# Camera.net
KiCad netlist of a schematic drawn in Altium Designer
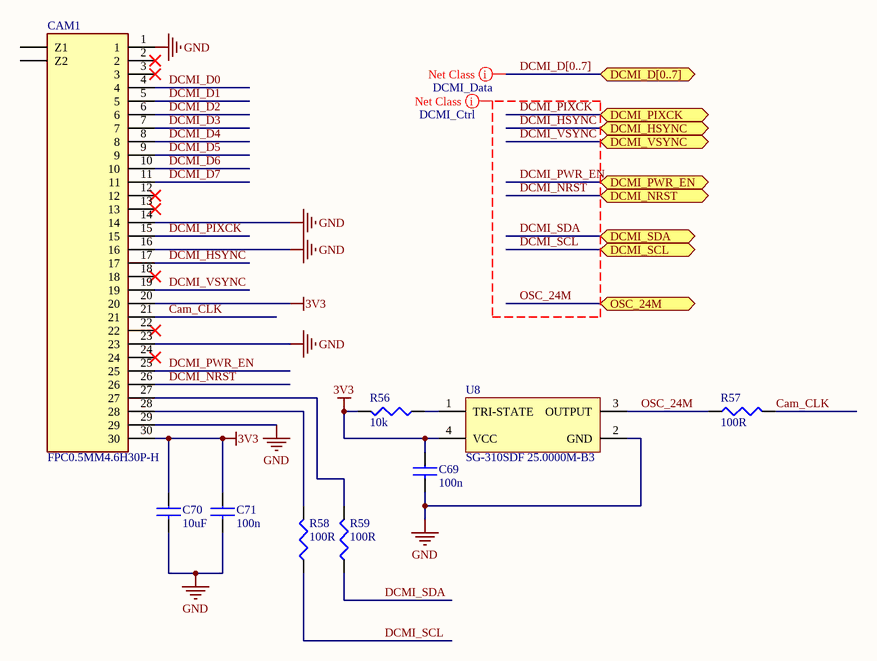
[diagram p0: Camera.SchDoc]

(export (version "E")
  (design (tool "Eeschema 10.0.6"))
  (components
    (comp (ref "C69")
      (value "100n")
      (footprint "C0402")
      (description "CAP CER .10UF 50V X5R 10% 0402")
      (fields
        (field (name "MANUFACTURER") "TDK Corporation")
        (field (name "MANUFACTURER PART NUMBER") "C1005X5R1H104K")
      )
      (libsource (lib "iMX6_Rex_Development_Baseboard_V1I1") (part "C1005X5R1H104K"))
    )
    (comp (ref "C70")
      (value "10uF")
      (footprint "C0402")
      (description "CAP CER 4.7UF 10V 20% X5R 0402")
      (fields
        (field (name "MANUFACTURER") "TDK Corporation")
        (field (name "MANUFACTURER PART NUMBER") "C1005X5R1A475M")
        (field (name ".CHECKED PCB") "RF")
        (field (name ".CHECKED SCH") "RF")
      )
      (libsource (lib "iMX6_Rex_Development_Baseboard_V1I1") (part "C1005X5R1A475M"))
    )
    (comp (ref "C71")
      (value "100n")
      (footprint "C0402")
      (description "CAP CER .10UF 50V X5R 10% 0402")
      (fields
        (field (name "MANUFACTURER") "TDK Corporation")
        (field (name "MANUFACTURER PART NUMBER") "C1005X5R1H104K")
      )
      (libsource (lib "iMX6_Rex_Development_Baseboard_V1I1") (part "C1005X5R1H104K"))
    )
    (comp (ref "CAM1")
      (value "FPC0.5MM4.6H30P-H")
      (footprint "FPC30P")
      (description "Connector")
      (fields
        (field (name "MANUFACTURER_PART_NUMBER") "006200307032800+")
        (field (name "MOUSER PART NUMBER") "581-006200307032800+")
      )
      (libsource (lib "fpc30") (part "FPC30"))
    )
    (comp (ref "R56")
      (value "10k")
      (footprint "R0402")
      (description "RES 10.0K OHM 1/16W 1% 0402 SMD")
      (fields
        (field (name "MANUFACTURER") "Yageo")
        (field (name "MANUFACTURER PART NUMBER") "RC0402FR-0710KL")
      )
      (libsource (lib "iMX6_Rex_Development_Baseboard_V1I1") (part "RC0402FR-0710KL"))
    )
    (comp (ref "R57")
      (value "100R")
      (footprint "R0402")
      (description "RES 100 OHM 1/16W 1% 0402 SMD")
      (fields
        (field (name "MANUFACTURER") "Yageo")
        (field (name "MANUFACTURER PART NUMBER") "RC0402FR-07100RL")
        (field (name ".CHECKED PCB") "RF")
        (field (name ".CHECKED SCH") "RF")
      )
      (libsource (lib "iMX6_Rex_Development_Baseboard_V1I1") (part "RC0402FR-07100RL"))
    )
    (comp (ref "R58")
      (value "100R")
      (footprint "R0402")
      (description "RES 100 OHM 1/16W 1% 0402 SMD")
      (fields
        (field (name "MANUFACTURER") "Yageo")
        (field (name "MANUFACTURER PART NUMBER") "RC0402FR-07100RL")
        (field (name ".CHECKED PCB") "RF")
        (field (name ".CHECKED SCH") "RF")
      )
      (libsource (lib "iMX6_Rex_Development_Baseboard_V1I1") (part "RC0402FR-07100RL"))
    )
    (comp (ref "R59")
      (value "100R")
      (footprint "R0402")
      (description "RES 100 OHM 1/16W 1% 0402 SMD")
      (fields
        (field (name "MANUFACTURER") "Yageo")
        (field (name "MANUFACTURER PART NUMBER") "RC0402FR-07100RL")
        (field (name ".CHECKED PCB") "RF")
        (field (name ".CHECKED SCH") "RF")
      )
      (libsource (lib "iMX6_Rex_Development_Baseboard_V1I1") (part "RC0402FR-07100RL"))
    )
    (comp (ref "U8")
      (value "SG-310SDF 25.0000M-B3")
      (footprint "EPSON-SG-310-4_V")
      (description "Crystal Oscillator (SPXO), 2.5 V, 25 MHz, -20 to 70 degC, 4-Pin SMD, RoHS, Tape and Reel")
      (libsource (lib "MiniPC") (part "CMP-1695-00002-3"))
    )
  )
  (nets
    (net (code "1") (name "/Cam_CLK") (class "Default")
      (node (ref "CAM1") (pin "21") (pinfunction "21_21") (pintype "passive"))
      (node (ref "R57") (pin "2") (pinfunction "2_2") (pintype "passive"))
    )
    (net (code "2") (name "/DCMI_D0") (class "Default")
      (node (ref "CAM1") (pin "4") (pinfunction "4_4") (pintype "passive"))
    )
    (net (code "3") (name "/DCMI_D1") (class "Default")
      (node (ref "CAM1") (pin "5") (pinfunction "5_5") (pintype "passive"))
    )
    (net (code "4") (name "/DCMI_D2") (class "Default")
      (node (ref "CAM1") (pin "6") (pinfunction "6_6") (pintype "passive"))
    )
    (net (code "5") (name "/DCMI_D3") (class "Default")
      (node (ref "CAM1") (pin "7") (pinfunction "7_7") (pintype "passive"))
    )
    (net (code "6") (name "/DCMI_D4") (class "Default")
      (node (ref "CAM1") (pin "8") (pinfunction "8_8") (pintype "passive"))
    )
    (net (code "7") (name "/DCMI_D5") (class "Default")
      (node (ref "CAM1") (pin "9") (pinfunction "9_9") (pintype "passive"))
    )
    (net (code "8") (name "/DCMI_D6") (class "Default")
      (node (ref "CAM1") (pin "10") (pinfunction "10_10") (pintype "passive"))
    )
    (net (code "9") (name "/DCMI_D7") (class "Default")
      (node (ref "CAM1") (pin "11") (pinfunction "11_11") (pintype "passive"))
    )
    (net (code "11") (name "/DCMI_HSYNC") (class "Default")
      (node (ref "CAM1") (pin "17") (pinfunction "17_17") (pintype "passive"))
    )
    (net (code "12") (name "/DCMI_NRST") (class "Default")
      (node (ref "CAM1") (pin "26") (pinfunction "26_26") (pintype "passive"))
    )
    (net (code "13") (name "/DCMI_PIXCK") (class "Default")
      (node (ref "CAM1") (pin "15") (pinfunction "15_15") (pintype "passive"))
    )
    (net (code "14") (name "/DCMI_PWR_EN") (class "Default")
      (node (ref "CAM1") (pin "25") (pinfunction "25_25") (pintype "passive"))
    )
    (net (code "15") (name "/DCMI_SCL") (class "Default")
      (node (ref "R58") (pin "1") (pinfunction "1_1") (pintype "passive"))
    )
    (net (code "16") (name "/DCMI_SDA") (class "Default")
      (node (ref "R59") (pin "1") (pinfunction "1_1") (pintype "passive"))
    )
    (net (code "17") (name "/DCMI_VSYNC") (class "Default")
      (node (ref "CAM1") (pin "19") (pinfunction "19_19") (pintype "passive"))
    )
    (net (code "18") (name "/OSC_24M") (class "Default")
      (node (ref "R57") (pin "1") (pinfunction "1_1") (pintype "passive"))
      (node (ref "U8") (pin "3") (pinfunction "OUTPUT_3") (pintype "passive"))
    )
    (net (code "19") (name "3V3") (class "Default")
      (node (ref "C69") (pin "1") (pinfunction "1_1") (pintype "passive"))
      (node (ref "C70") (pin "1") (pinfunction "1_1") (pintype "passive"))
      (node (ref "C71") (pin "1") (pinfunction "1_1") (pintype "passive"))
      (node (ref "CAM1") (pin "20") (pinfunction "20_20") (pintype "passive"))
      (node (ref "CAM1") (pin "30") (pinfunction "30_30") (pintype "passive"))
      (node (ref "R56") (pin "2") (pinfunction "2_2") (pintype "passive"))
      (node (ref "U8") (pin "4") (pinfunction "VCC_4") (pintype "power_in"))
    )
    (net (code "20") (name "GND") (class "Default")
      (node (ref "C69") (pin "2") (pinfunction "2_2") (pintype "passive"))
      (node (ref "C70") (pin "2") (pinfunction "2_2") (pintype "passive"))
      (node (ref "C71") (pin "2") (pinfunction "2_2") (pintype "passive"))
      (node (ref "CAM1") (pin "1") (pinfunction "1_1") (pintype "passive"))
      (node (ref "CAM1") (pin "14") (pinfunction "14_14") (pintype "passive"))
      (node (ref "CAM1") (pin "16") (pinfunction "16_16") (pintype "passive"))
      (node (ref "CAM1") (pin "23") (pinfunction "23_23") (pintype "passive"))
      (node (ref "CAM1") (pin "29") (pinfunction "29_29") (pintype "passive"))
      (node (ref "U8") (pin "2") (pinfunction "GND_2") (pintype "power_in"))
    )
    (net (code "21") (name "Net-(CAM1-Pad27)") (class "Default")
      (node (ref "CAM1") (pin "27") (pinfunction "27_27") (pintype "passive"))
      (node (ref "R59") (pin "2") (pinfunction "2_2") (pintype "passive"))
    )
    (net (code "22") (name "Net-(CAM1-Pad28)") (class "Default")
      (node (ref "CAM1") (pin "28") (pinfunction "28_28") (pintype "passive"))
      (node (ref "R58") (pin "2") (pinfunction "2_2") (pintype "passive"))
    )
    (net (code "23") (name "Net-(U8-TRI-STATE)") (class "Default")
      (node (ref "R56") (pin "1") (pinfunction "1_1") (pintype "passive"))
      (node (ref "U8") (pin "1") (pinfunction "TRI-STATE_1") (pintype "passive"))
    )
    (net (code "24") (name "unconnected-(CAM1-Pad2)") (class "Default")
      (node (ref "CAM1") (pin "2") (pinfunction "2_2") (pintype "passive+no_connect"))
    )
    (net (code "25") (name "unconnected-(CAM1-Pad3)") (class "Default")
      (node (ref "CAM1") (pin "3") (pinfunction "3_3") (pintype "passive+no_connect"))
    )
    (net (code "26") (name "unconnected-(CAM1-Pad12)") (class "Default")
      (node (ref "CAM1") (pin "12") (pinfunction "12_12") (pintype "passive+no_connect"))
    )
    (net (code "27") (name "unconnected-(CAM1-Pad13)") (class "Default")
      (node (ref "CAM1") (pin "13") (pinfunction "13_13") (pintype "passive+no_connect"))
    )
    (net (code "28") (name "unconnected-(CAM1-Pad18)") (class "Default")
      (node (ref "CAM1") (pin "18") (pinfunction "18_18") (pintype "passive+no_connect"))
    )
    (net (code "29") (name "unconnected-(CAM1-Pad22)") (class "Default")
      (node (ref "CAM1") (pin "22") (pinfunction "22_22") (pintype "passive+no_connect"))
    )
    (net (code "30") (name "unconnected-(CAM1-Pad24)") (class "Default")
      (node (ref "CAM1") (pin "24") (pinfunction "24_24") (pintype "passive+no_connect"))
    )
    (net (code "31") (name "unconnected-(CAM1-PadZ1)") (class "Default")
      (node (ref "CAM1") (pin "Z1") (pinfunction "Z1_Z1") (pintype "passive"))
    )
    (net (code "32") (name "unconnected-(CAM1-PadZ2)") (class "Default")
      (node (ref "CAM1") (pin "Z2") (pinfunction "Z2_Z2") (pintype "passive"))
    )
  )
)
